# -NEW_AQB-5-ANTON_TRANS-PWR-TVS.net
KiCad netlist of a schematic drawn in Altium Designer
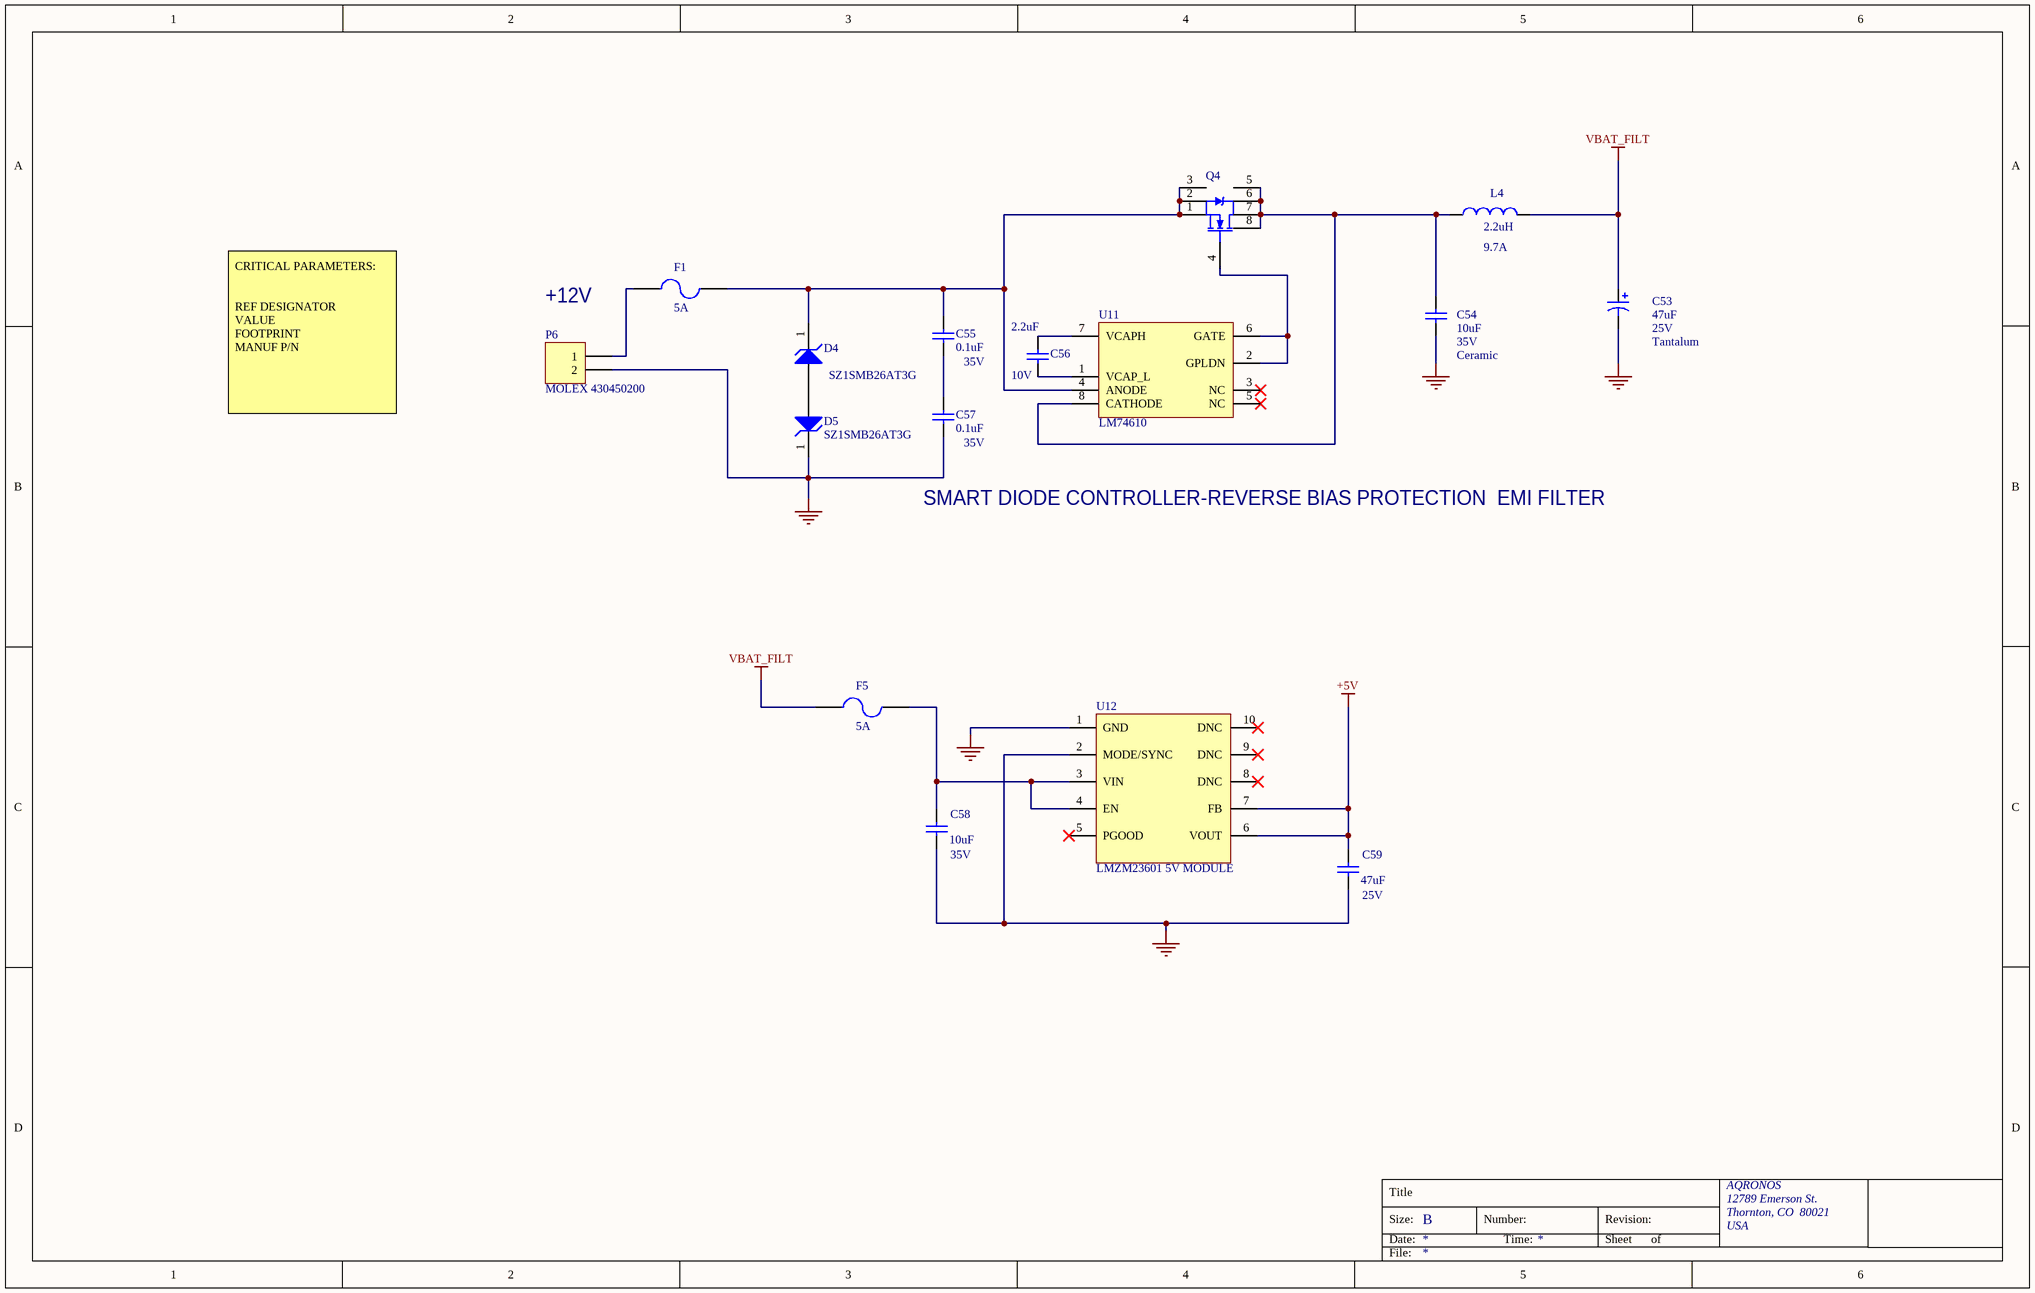
[diagram p0: -NEW_AQB-5-ANTON_TRANS-PWR-TVS.SchDoc]

(export (version "E")
  (design (tool "Eeschema 10.0.6"))
  (components
    (comp (ref "C53")
      (value "Tantalum")
      (footprint "C2917")
      (description "CAP TANT 47UF 20% 25V 2917")
      (fields
        (field (name "DISTRIBUTOR PART NUMBER") "478-4120-1-ND")
        (field (name "MANUFACTURER PART NUMBER") "TPSD476M025R0250")
        (field (name "VOLTAGE") "25V")
        (field (name "ALTIUM_VALUE") "47uF")
      )
      (libsource (lib "AQRONOS_TEMP_SCH") (part "Capacitor-Polarized"))
    )
    (comp (ref "C54")
      (value "Ceramic")
      (footprint "CAP1206")
      (description "CAP CER 10UF 35V X7R 1206")
      (fields
        (field (name "DISTRIBUTOR PART NUMBER") "445-174428-1-ND")
        (field (name "MANUFACTURER PART NUMBER") "CGA5L1X7R1V106K160AC")
        (field (name "VOLTAGE") "35V")
        (field (name "ALTIUM_VALUE") "10uF")
      )
      (libsource (lib "AQRONOS_TEMP_SCH") (part "Capacitor_non_pol"))
    )
    (comp (ref "C55")
      (value "0.1uF")
      (footprint "CAP0603")
      (description "CAP CER 0.1UF 35V X7R 0603")
      (fields
        (field (name "DISTRIBUTOR PART NUMBER") "587-3354-1-ND")
        (field (name "MANUFACTURER PART NUMBER") "GMK107B7104KAHT")
        (field (name "VOLTAGE") "35V")
      )
      (libsource (lib "AQRONOS_TEMP_SCH") (part "Capacitor_non_pol"))
    )
    (comp (ref "C56")
      (value "Capacitor_non_pol")
      (footprint "CAP0603")
      (description "CAP CER 2.2UF 10V X7R 0603")
      (fields
        (field (name "MANUFACTURER PART NUMBER") "GRM188R71A225KE15D")
        (field (name "ALTIUM_VALUE") "2.2uF")
        (field (name "VOLTAGE") "10V")
        (field (name "DISTRIBUTOR PART NUMBER") "490-4520-1-ND")
      )
      (libsource (lib "AQRONOS_TEMP_SCH") (part "Capacitor_non_pol"))
    )
    (comp (ref "C57")
      (value "0.1uF")
      (footprint "CAP0603")
      (description "CAP CER 0.1UF 35V X7R 0603")
      (fields
        (field (name "DISTRIBUTOR PART NUMBER") "587-3354-1-ND")
        (field (name "MANUFACTURER PART NUMBER") "GMK107B7104KAHT")
        (field (name "VOLTAGE") "35V")
      )
      (libsource (lib "AQRONOS_TEMP_SCH") (part "Capacitor_non_pol"))
    )
    (comp (ref "C58")
      (value "10uF")
      (footprint "CAP1206")
      (description "Capacitor_non_pol")
      (fields
        (field (name "DISTRIBUTOR PART NUMBER") "445-14417-1-ND")
        (field (name "MANUFACTURER PART NUMBER") "C2012X5R1V106K085AC")
        (field (name "VOLTAGE") "35V")
      )
      (libsource (lib "AQRONOS_TEMP_SCH") (part "Capacitor_non_pol"))
    )
    (comp (ref "C59")
      (value "47uF")
      (footprint "CAP1206")
      (description "Capacitor_non_pol")
      (fields
        (field (name "DISTRIBUTOR PART NUMBER") "490-16268-1-ND")
        (field (name "MANUFACTURER PART NUMBER") "GRM31CR61E476ME44L")
        (field (name "VOLTAGE") "25V")
      )
      (libsource (lib "AQRONOS_TEMP_SCH") (part "Capacitor_non_pol"))
    )
    (comp (ref "D4")
      (value "Diode Zener")
      (description "TVS DIODE 26V 42.1V SMB")
      (fields
        (field (name "DISTRIBUTOR PART NUMBER") "F11556CT-ND")
        (field (name "MANUFACTURER PART NUMBER") "SZ1SMB26AT3G")
        (field (name "PUBLISHER") "Altium Limited")
      )
      (libsource (lib "AQRONOS_TEMP_SCH") (part "Diode Zener"))
    )
    (comp (ref "D5")
      (value "Diode Zener")
      (description "TVS DIODE 26V 42.1V SMB")
      (fields
        (field (name "DISTRIBUTOR PART NUMBER") "F11556CT-ND")
        (field (name "MANUFACTURER PART NUMBER") "SZ1SMB26AT3G")
        (field (name "PUBLISHER") "Altium Limited")
      )
      (libsource (lib "AQRONOS_TEMP_SCH") (part "Diode Zener"))
    )
    (comp (ref "F1")
      (value "Fuse")
      (footprint "RES0603")
      (description "FUSE BOARD MNT 5A 32VAC/VDC 0603")
      (fields
        (field (name "MANUFACTURER PART NUMBER") "TR/0603FA5-R")
        (field (name "MANUFACTURER") "Eaton")
        (field (name "CURRENT") "5A")
        (field (name "PUBLISHER") "Altium Limited")
      )
      (libsource (lib "AQRONOS_TEMP_SCH") (part "Fuse"))
    )
    (comp (ref "F5")
      (value "Fuse")
      (footprint "RES0603")
      (description "FUSE BOARD MNT 5A 32VAC/VDC 0603")
      (fields
        (field (name "MANUFACTURER PART NUMBER") "TR/0603FA5-R")
        (field (name "MANUFACTURER") "Eaton")
        (field (name "CURRENT") "5A")
        (field (name "PUBLISHER") "Altium Limited")
      )
      (libsource (lib "AQRONOS_TEMP_SCH") (part "Fuse"))
    )
    (comp (ref "L4")
      (value "2.2uH")
      (description "Fixed Inductor 2.2uH 20% 9.7A 14.5mOhms AEC-Q200")
      (fields
        (field (name "DISTRIBUTOR PART NUMBER") "994-XAL5030-222MEB")
        (field (name "MANUFACTURER") "Coilcraft")
        (field (name "CURRENT") "9.7A")
      )
      (libsource (lib "AQRONOS_TEMP_SCH") (part "Inductor"))
    )
    (comp (ref "P6")
      (value "MOLEX 430450200")
      (footprint "RA-HDR1X2")
      (description "Connector Header Through Hole, Right Angle 2 position")
      (fields
        (field (name "MANUFACTURER PART NUMBER") "0430450200")
        (field (name "DISTRIBUTOR PART NUMBER") "WM1813-ND")
      )
      (libsource (lib "AQRONOS-Released") (part "HDR1x2-430450200"))
    )
    (comp (ref "Q4")
      (value "CSD18531Q5A")
      (description "N-Channel 2.5V (G-S) MOSFET")
      (fields
        (field (name "DISTRIBUTOR PART NUMBER") "296-30573-1-ND")
        (field (name "PUBLISHER") "Altium Limited")
      )
      (libsource (lib "AQRONOS_TEMP_SCH") (part "CSD18531Q5A"))
    )
    (comp (ref "U11")
      (value "LM74610")
      (footprint "8-TSSOP-VSSOP")
      (description "IC SMART DIODE CTLR 8VSSOP")
      (fields
        (field (name "DISTRIBUTOR PART NUMBER") "296-43067-1-ND")
        (field (name "MANUFACTURER") "Texas Instruments")
      )
      (libsource (lib "AQRONOS_TEMP_SCH") (part "LM74610"))
    )
    (comp (ref "U12")
      (value "LMZM23601 5V MODULE")
      (fields
        (field (name "MANUFACTURER PART NUMBER") "LMZM23601V3SILT")
        (field (name "DISTRIBUTOR PART NUMBER") "296-49461-1-ND")
      )
      (libsource (lib "AQRONOS_TEMP_SCH") (part "LMZM23601 5V MODULE"))
    )
  )
  (nets
    (net (code "1") (name "+5V") (class "Default")
      (node (ref "C59") (pin "1") (pinfunction "1_1") (pintype "passive"))
      (node (ref "U12") (pin "6") (pinfunction "VOUT_6") (pintype "passive"))
      (node (ref "U12") (pin "7") (pinfunction "FB_7") (pintype "passive"))
    )
    (net (code "2") (name "GND") (class "Default")
      (node (ref "C53") (pin "2") (pinfunction "2_2") (pintype "passive"))
      (node (ref "C54") (pin "2") (pinfunction "2_2") (pintype "passive"))
      (node (ref "C57") (pin "1") (pinfunction "1_1") (pintype "passive"))
      (node (ref "C58") (pin "2") (pinfunction "2_2") (pintype "passive"))
      (node (ref "C59") (pin "2") (pinfunction "2_2") (pintype "passive"))
      (node (ref "D5") (pin "1") (pinfunction "K_1") (pintype "passive"))
      (node (ref "P6") (pin "2") (pinfunction "2_2") (pintype "passive"))
      (node (ref "U12") (pin "1") (pinfunction "GND_1") (pintype "passive"))
      (node (ref "U12") (pin "2") (pinfunction "MODE/SYNC_2") (pintype "passive"))
    )
    (net (code "3") (name "Net-(C55-Pad1)") (class "Default")
      (node (ref "C55") (pin "1") (pinfunction "1_1") (pintype "passive"))
      (node (ref "C57") (pin "2") (pinfunction "2_2") (pintype "passive"))
    )
    (net (code "4") (name "Net-(D4-A)") (class "Default")
      (node (ref "D4") (pin "2") (pinfunction "A_2") (pintype "passive"))
      (node (ref "D5") (pin "2") (pinfunction "A_2") (pintype "passive"))
    )
    (net (code "5") (name "Net-(D4-K)") (class "Default")
      (node (ref "C55") (pin "2") (pinfunction "2_2") (pintype "passive"))
      (node (ref "D4") (pin "1") (pinfunction "K_1") (pintype "passive"))
      (node (ref "F1") (pin "2") (pinfunction "2_2") (pintype "passive"))
      (node (ref "Q4") (pin "1") (pinfunction "S_1") (pintype "passive"))
      (node (ref "Q4") (pin "2") (pinfunction "S_2") (pintype "passive"))
      (node (ref "Q4") (pin "3") (pinfunction "S_3") (pintype "passive"))
      (node (ref "U11") (pin "4") (pinfunction "ANODE_4") (pintype "power_in"))
    )
    (net (code "6") (name "Net-(F1-Pad1)") (class "Default")
      (node (ref "F1") (pin "1") (pinfunction "1_1") (pintype "passive"))
      (node (ref "P6") (pin "1") (pinfunction "1_1") (pintype "passive"))
    )
    (net (code "7") (name "Net-(Q4-G)") (class "Default")
      (node (ref "Q4") (pin "4") (pinfunction "G_4") (pintype "passive"))
      (node (ref "U11") (pin "2") (pinfunction "GPLDN_2") (pintype "passive"))
      (node (ref "U11") (pin "6") (pinfunction "GATE_6") (pintype "open_collector"))
    )
    (net (code "8") (name "Net-(U11-CATHODE)") (class "Default")
      (node (ref "C54") (pin "1") (pinfunction "1_1") (pintype "passive"))
      (node (ref "L4") (pin "1") (pinfunction "1_1") (pintype "passive"))
      (node (ref "Q4") (pin "5") (pinfunction "D_5") (pintype "passive"))
      (node (ref "Q4") (pin "6") (pinfunction "D_6") (pintype "passive"))
      (node (ref "Q4") (pin "7") (pinfunction "D_7") (pintype "passive"))
      (node (ref "Q4") (pin "8") (pinfunction "D_8") (pintype "passive"))
      (node (ref "U11") (pin "8") (pinfunction "CATHODE_8") (pintype "power_in"))
    )
    (net (code "9") (name "Net-(U11-VCAPH)") (class "Default")
      (node (ref "C56") (pin "2") (pinfunction "2_2") (pintype "passive"))
      (node (ref "U11") (pin "7") (pinfunction "VCAPH_7") (pintype "passive"))
    )
    (net (code "10") (name "Net-(U11-VCAP_L)") (class "Default")
      (node (ref "C56") (pin "1") (pinfunction "1_1") (pintype "passive"))
      (node (ref "U11") (pin "1") (pinfunction "VCAP_L_1") (pintype "passive"))
    )
    (net (code "11") (name "Net-(U12-EN)") (class "Default")
      (node (ref "C58") (pin "1") (pinfunction "1_1") (pintype "passive"))
      (node (ref "F5") (pin "2") (pinfunction "2_2") (pintype "passive"))
      (node (ref "U12") (pin "3") (pinfunction "VIN_3") (pintype "passive"))
      (node (ref "U12") (pin "4") (pinfunction "EN_4") (pintype "passive"))
    )
    (net (code "12") (name "VBAT_FILT") (class "Default")
      (node (ref "C53") (pin "1") (pinfunction "1_1") (pintype "passive"))
      (node (ref "F5") (pin "1") (pinfunction "1_1") (pintype "passive"))
      (node (ref "L4") (pin "2") (pinfunction "2_2") (pintype "passive"))
    )
    (net (code "13") (name "unconnected-(U11-NC-Pad3)") (class "Default")
      (node (ref "U11") (pin "3") (pinfunction "NC_3") (pintype "passive+no_connect"))
    )
    (net (code "14") (name "unconnected-(U11-NC-Pad5)") (class "Default")
      (node (ref "U11") (pin "5") (pinfunction "NC_5") (pintype "open_collector+no_connect"))
    )
    (net (code "15") (name "unconnected-(U12-DNC-Pad8)") (class "Default")
      (node (ref "U12") (pin "8") (pinfunction "DNC_8") (pintype "passive+no_connect"))
    )
    (net (code "16") (name "unconnected-(U12-DNC-Pad9)") (class "Default")
      (node (ref "U12") (pin "9") (pinfunction "DNC_9") (pintype "passive+no_connect"))
    )
    (net (code "17") (name "unconnected-(U12-DNC-Pad10)") (class "Default")
      (node (ref "U12") (pin "10") (pinfunction "DNC_10") (pintype "passive+no_connect"))
    )
    (net (code "18") (name "unconnected-(U12-PGOOD-Pad5)") (class "Default")
      (node (ref "U12") (pin "5") (pinfunction "PGOOD_5") (pintype "passive+no_connect"))
    )
  )
)
